# PROJECT-TSC_v66.net
KiCad netlist of a schematic drawn in EAGLE
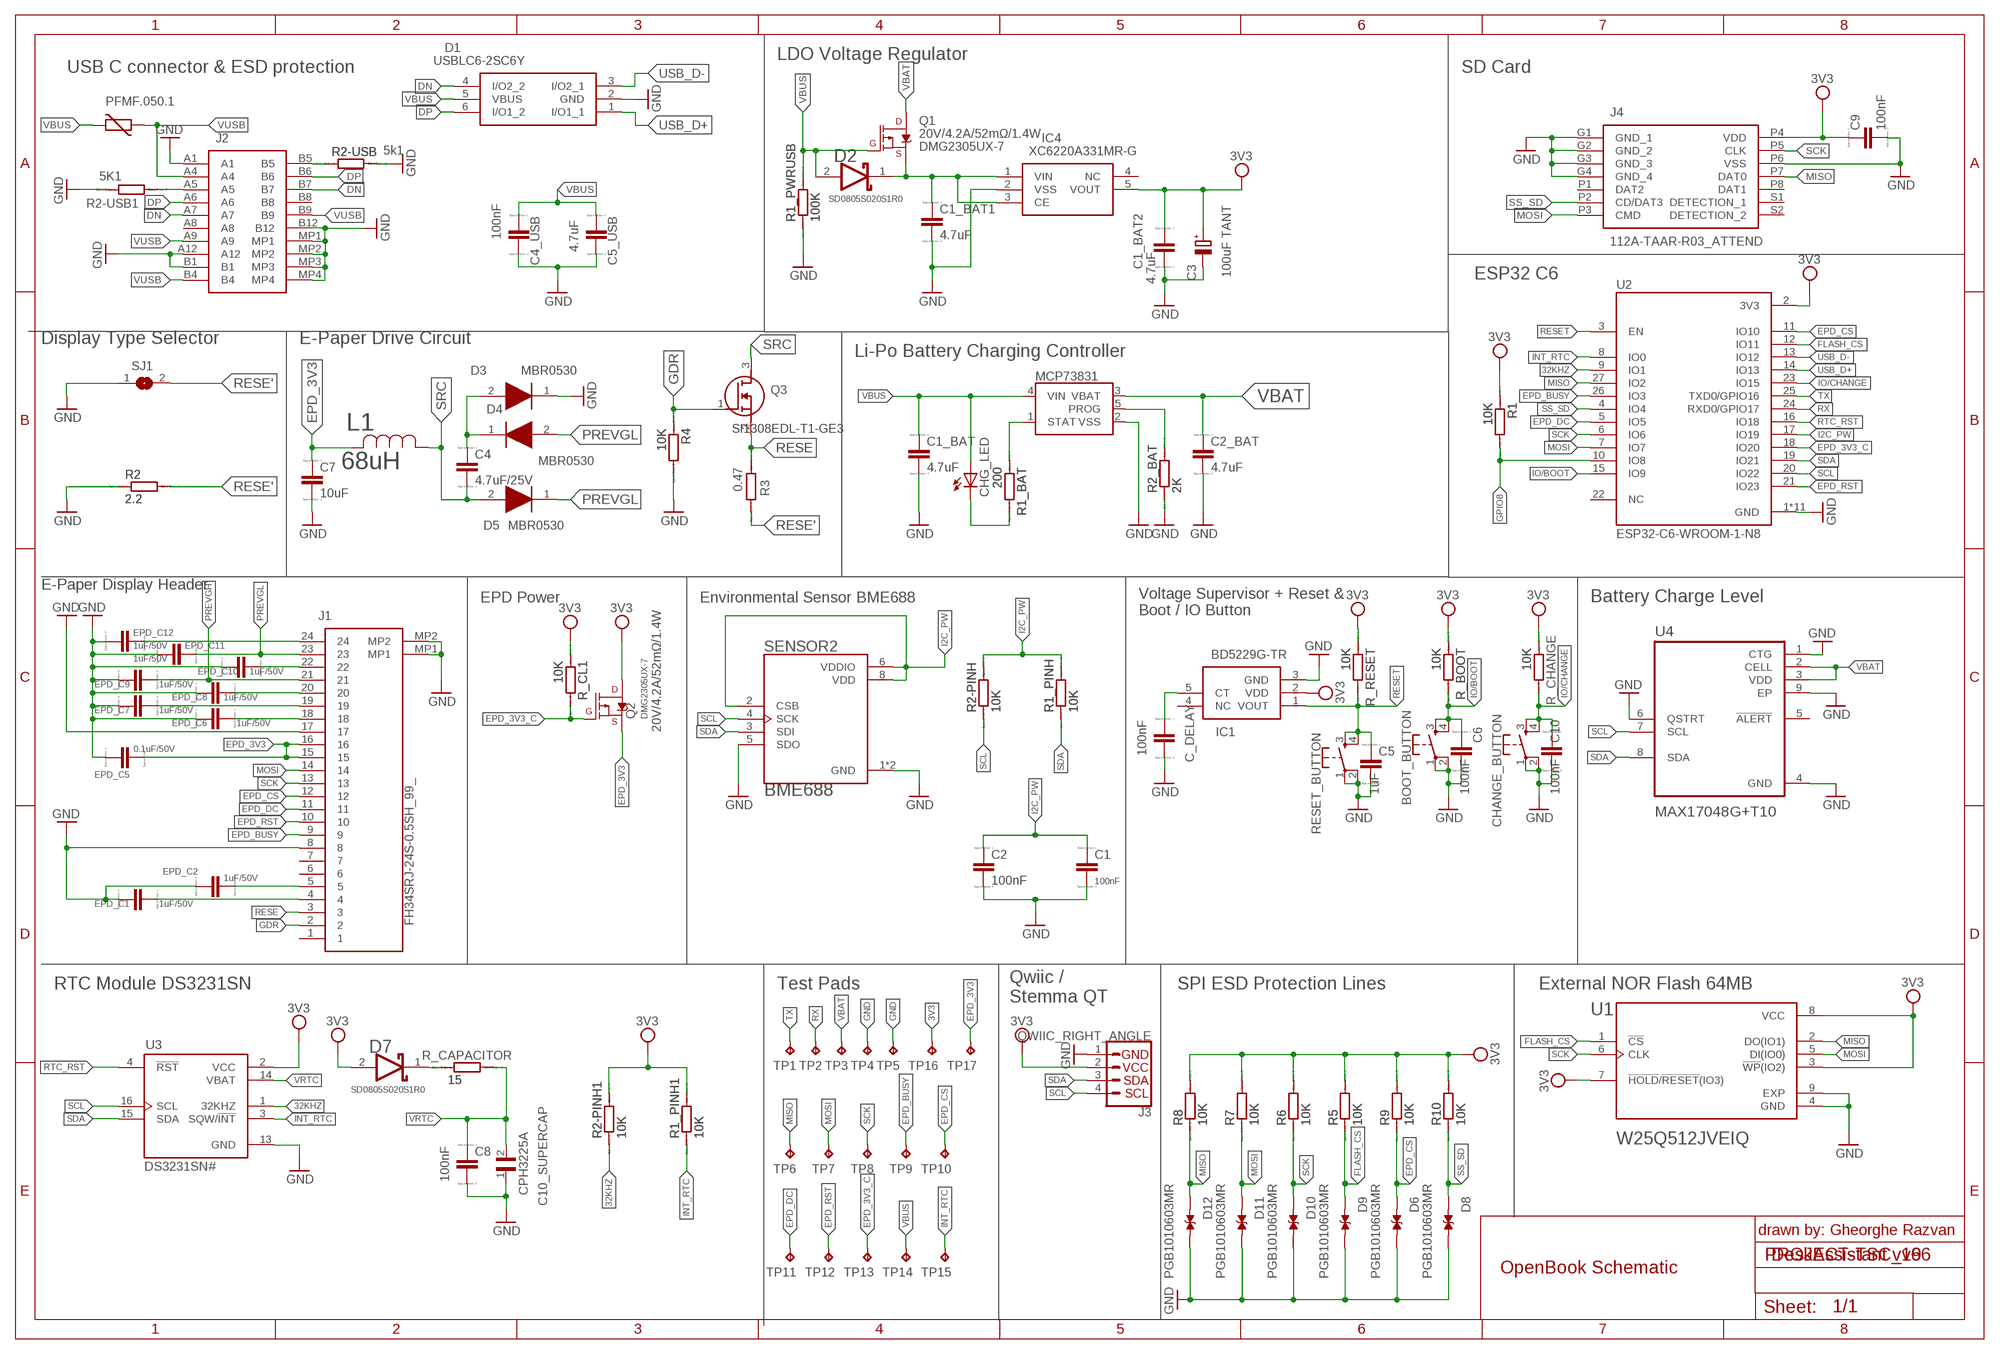
[diagram p0: schematic, sheet 1]

(export (version "E")
  (design (tool "Eeschema 10.0.6"))
  (components
    (comp (ref "BOOT_BUTTON")
      (value "BUTTON_CUSYOMV1")
      (footprint "eagle-import:MYBUTTON")
      (libsource (lib "eagle-import") (part "BUTTON_CUSYOMV1"))
    )
    (comp (ref "C1")
      (value "100nF")
      (footprint "eagle-import:EAGLE-LTSPICE_C0402")
      (libsource (lib "eagle-import") (part "EAGLE-LTSPICE_CC0402"))
    )
    (comp (ref "C1_BAT")
      (value "4.7uF")
      (footprint "eagle-import:EAGLE-LTSPICE_C0402")
      (libsource (lib "eagle-import") (part "ESP32_WROVER_EAGLE-LTSPICE_CC0402"))
    )
    (comp (ref "C1_BAT1")
      (value "4.7uF")
      (footprint "eagle-import:EAGLE-LTSPICE_C0402")
      (libsource (lib "eagle-import") (part "ESP32_WROVER_EAGLE-LTSPICE_CC0402"))
    )
    (comp (ref "C1_BAT2")
      (value "4.7uF")
      (footprint "eagle-import:EAGLE-LTSPICE_C0402")
      (libsource (lib "eagle-import") (part "ESP32_WROVER_EAGLE-LTSPICE_CC0402"))
    )
    (comp (ref "C2")
      (value "100nF")
      (footprint "eagle-import:EAGLE-LTSPICE_C0402")
      (libsource (lib "eagle-import") (part "EAGLE-LTSPICE_CC0402"))
    )
    (comp (ref "C2_BAT")
      (value "4.7uF")
      (footprint "eagle-import:EAGLE-LTSPICE_C0402")
      (libsource (lib "eagle-import") (part "ESP32_WROVER_EAGLE-LTSPICE_CC0402"))
    )
    (comp (ref "C3")
      (value "100uF TANT")
      (footprint "eagle-import:RCL_CT3528")
      (libsource (lib "eagle-import") (part "RCL_CPOL-EUCT3528"))
    )
    (comp (ref "C4")
      (value "4.7uF/25V")
      (footprint "eagle-import:EAGLE-LTSPICE_C0402")
      (libsource (lib "eagle-import") (part "ESP32_WROVER_EAGLE-LTSPICE_CC0402"))
    )
    (comp (ref "C4_USB")
      (value "100nF")
      (footprint "eagle-import:EAGLE-LTSPICE_C0402")
      (libsource (lib "eagle-import") (part "ESP32_WROVER_EAGLE-LTSPICE_CC0402"))
    )
    (comp (ref "C5")
      (value "1uF")
      (footprint "eagle-import:EAGLE-LTSPICE_C0402")
      (libsource (lib "eagle-import") (part "EAGLE-LTSPICE_CC0402"))
    )
    (comp (ref "C5_USB")
      (value "4.7uF")
      (footprint "eagle-import:EAGLE-LTSPICE_C0402")
      (libsource (lib "eagle-import") (part "ESP32_WROVER_EAGLE-LTSPICE_CC0402"))
    )
    (comp (ref "C6")
      (value "100nF")
      (footprint "eagle-import:EAGLE-LTSPICE_C0402")
      (libsource (lib "eagle-import") (part "EAGLE-LTSPICE_CC0402"))
    )
    (comp (ref "C7")
      (value "10uF")
      (footprint "eagle-import:EAGLE-LTSPICE_C0402")
      (libsource (lib "eagle-import") (part "EAGLE-LTSPICE_CC0402"))
    )
    (comp (ref "C8")
      (value "100nF")
      (footprint "eagle-import:EAGLE-LTSPICE_C0402")
      (libsource (lib "eagle-import") (part "ESP32_WROVER_EAGLE-LTSPICE_CC0402"))
    )
    (comp (ref "C9")
      (value "100nF")
      (footprint "eagle-import:EAGLE-LTSPICE_C0402")
      (libsource (lib "eagle-import") (part "ESP32_WROVER_EAGLE-LTSPICE_CC0402"))
    )
    (comp (ref "C10")
      (value "100nF")
      (footprint "eagle-import:EAGLE-LTSPICE_C0402")
      (libsource (lib "eagle-import") (part "EAGLE-LTSPICE_CC0402"))
    )
    (comp (ref "C10_SUPERCAP")
      (value "CPH3225A")
      (footprint "eagle-import:CAPCP3225X100N")
      (fields (field (name "MF") "Seiko Instruments"))
      (libsource (lib "eagle-import") (part "CPH3225A"))
    )
    (comp (ref "CHANGE_BUTTON")
      (value "BUTTON_CUSYOMV1")
      (footprint "eagle-import:MYBUTTON")
      (libsource (lib "eagle-import") (part "BUTTON_CUSYOMV1"))
    )
    (comp (ref "CHG_LED")
      (value "ADAFRUIT_LEDCHIP-LED0603")
      (footprint "eagle-import:ADAFRUIT_CHIP-LED0603")
      (libsource (lib "eagle-import") (part "ADAFRUIT_LEDCHIP-LED0603"))
    )
    (comp (ref "C_DELAY")
      (value "100nF")
      (footprint "eagle-import:EAGLE-LTSPICE_C0402")
      (libsource (lib "eagle-import") (part "EAGLE-LTSPICE_CC0402"))
    )
    (comp (ref "D1")
      (value "USBLC6-2SC6Y")
      (footprint "eagle-import:SOT95P280X145-6N")
      (fields (field (name "MF") "STMicroelectronics"))
      (libsource (lib "eagle-import") (part "USBLC6-2SC6Y"))
    )
    (comp (ref "D2")
      (value "ESP32_WROVER_AVX---SD0805S020S1R0_AVX_SD0805S020S1R0_0_0AVX_SD0805S020S1R0_0_0")
      (footprint "eagle-import:ESP32_WROVER_AVX---SD0805S020S1R0_AVX_SD0805S020S1R0_0")
      (fields
        (field (name "DIGIKEY_PART_NUMBER") "478-7800-1-ND")
        (field (name "MF") "AVX")
        (field (name "MOUSER_PART_NUMBER") "581-SD0805S020S1R0")
      )
      (libsource (lib "eagle-import") (part "ESP32_WROVER_AVX---SD0805S020S1R0_AVX_SD0805S020S1R0_0_0AVX_SD0805S020S1R0_0_0"))
    )
    (comp (ref "D3")
      (value "MBR0530")
      (footprint "eagle-import:SOD3716X135N")
      (fields (field (name "MF") "ON Semiconductor"))
      (libsource (lib "eagle-import") (part "MBR0530"))
    )
    (comp (ref "D4")
      (value "MBR0530")
      (footprint "eagle-import:SOD3716X135N")
      (fields (field (name "MF") "ON Semiconductor"))
      (libsource (lib "eagle-import") (part "MBR0530"))
    )
    (comp (ref "D5")
      (value "MBR0530")
      (footprint "eagle-import:SOD3716X135N")
      (fields (field (name "MF") "ON Semiconductor"))
      (libsource (lib "eagle-import") (part "MBR0530"))
    )
    (comp (ref "D6")
      (value "PGB1010603MR")
      (footprint "eagle-import:DIOC1608X36N")
      (fields (field (name "MF") "Littelfuse Inc."))
      (libsource (lib "eagle-import") (part "PGB1010603MR"))
    )
    (comp (ref "D7")
      (value "ESP32_WROVER_AVX---SD0805S020S1R0_AVX_SD0805S020S1R0_0_0AVX_SD0805S020S1R0_0_0")
      (footprint "eagle-import:ESP32_WROVER_AVX---SD0805S020S1R0_AVX_SD0805S020S1R0_0")
      (fields
        (field (name "DIGIKEY_PART_NUMBER") "478-7800-1-ND")
        (field (name "MF") "AVX")
        (field (name "MOUSER_PART_NUMBER") "581-SD0805S020S1R0")
      )
      (libsource (lib "eagle-import") (part "ESP32_WROVER_AVX---SD0805S020S1R0_AVX_SD0805S020S1R0_0_0AVX_SD0805S020S1R0_0_0"))
    )
    (comp (ref "D8")
      (value "PGB1010603MR")
      (footprint "eagle-import:DIOC1608X36N")
      (fields (field (name "MF") "Littelfuse Inc."))
      (libsource (lib "eagle-import") (part "PGB1010603MR"))
    )
    (comp (ref "D9")
      (value "PGB1010603MR")
      (footprint "eagle-import:DIOC1608X36N")
      (fields (field (name "MF") "Littelfuse Inc."))
      (libsource (lib "eagle-import") (part "PGB1010603MR"))
    )
    (comp (ref "D10")
      (value "PGB1010603MR")
      (footprint "eagle-import:DIOC1608X36N")
      (fields (field (name "MF") "Littelfuse Inc."))
      (libsource (lib "eagle-import") (part "PGB1010603MR"))
    )
    (comp (ref "D11")
      (value "PGB1010603MR")
      (footprint "eagle-import:DIOC1608X36N")
      (fields (field (name "MF") "Littelfuse Inc."))
      (libsource (lib "eagle-import") (part "PGB1010603MR"))
    )
    (comp (ref "D12")
      (value "PGB1010603MR")
      (footprint "eagle-import:DIOC1608X36N")
      (fields (field (name "MF") "Littelfuse Inc."))
      (libsource (lib "eagle-import") (part "PGB1010603MR"))
    )
    (comp (ref "EPD_C1")
      (value "1uF/50V")
      (footprint "eagle-import:EAGLE-LTSPICE_C0402")
      (libsource (lib "eagle-import") (part "ESP32_WROVER_EAGLE-LTSPICE_CC0402"))
    )
    (comp (ref "EPD_C2")
      (value "1uF/50V")
      (footprint "eagle-import:EAGLE-LTSPICE_C0402")
      (libsource (lib "eagle-import") (part "ESP32_WROVER_EAGLE-LTSPICE_CC0402"))
    )
    (comp (ref "EPD_C5")
      (value "0.1uF/50V")
      (footprint "eagle-import:EAGLE-LTSPICE_C0402")
      (libsource (lib "eagle-import") (part "ESP32_WROVER_EAGLE-LTSPICE_CC0402"))
    )
    (comp (ref "EPD_C6")
      (value "1uF/50V")
      (footprint "eagle-import:EAGLE-LTSPICE_C0402")
      (libsource (lib "eagle-import") (part "ESP32_WROVER_EAGLE-LTSPICE_CC0402"))
    )
    (comp (ref "EPD_C7")
      (value "1uF/50V")
      (footprint "eagle-import:EAGLE-LTSPICE_C0402")
      (libsource (lib "eagle-import") (part "ESP32_WROVER_EAGLE-LTSPICE_CC0402"))
    )
    (comp (ref "EPD_C8")
      (value "1uF/50V")
      (footprint "eagle-import:EAGLE-LTSPICE_C0402")
      (libsource (lib "eagle-import") (part "ESP32_WROVER_EAGLE-LTSPICE_CC0402"))
    )
    (comp (ref "EPD_C9")
      (value "1uF/50V")
      (footprint "eagle-import:EAGLE-LTSPICE_C0402")
      (libsource (lib "eagle-import") (part "ESP32_WROVER_EAGLE-LTSPICE_CC0402"))
    )
    (comp (ref "EPD_C10")
      (value "1uF/50V")
      (footprint "eagle-import:EAGLE-LTSPICE_C0402")
      (libsource (lib "eagle-import") (part "ESP32_WROVER_EAGLE-LTSPICE_CC0402"))
    )
    (comp (ref "EPD_C11")
      (value "1uF/50V")
      (footprint "eagle-import:EAGLE-LTSPICE_C0402")
      (libsource (lib "eagle-import") (part "ESP32_WROVER_EAGLE-LTSPICE_CC0402"))
    )
    (comp (ref "EPD_C12")
      (value "1uF/50V")
      (footprint "eagle-import:EAGLE-LTSPICE_C0402")
      (libsource (lib "eagle-import") (part "ESP32_WROVER_EAGLE-LTSPICE_CC0402"))
    )
    (comp (ref "IC1")
      (value "BD5229G-TR")
      (footprint "eagle-import:SOT95P280X120-5N")
      (fields (field (name "MOUSER_PART_NUMBER") "755-BD5229G-TR"))
      (libsource (lib "eagle-import") (part "BD5229G-TR"))
    )
    (comp (ref "IC4")
      (value "XC6220A331MR-G")
      (footprint "eagle-import:SOT95P280X120-5N")
      (fields (field (name "MOUSER_PART_NUMBER") "865-XC6220A331MR-G"))
      (libsource (lib "eagle-import") (part "XC6220A331MR-G"))
    )
    (comp (ref "J1")
      (value "FH34SRJ-24S-0.5SH_99_")
      (footprint "eagle-import:FH34SRJ24S05SH99")
      (fields
        (field (name "MANUFACTURER_PART_NUMBER") "FH34SRJ-24S-0.5SH(99)")
        (field (name "MOUSER_PART_NUMBER") "798-FH34SRJ24S05SH99")
      )
      (libsource (lib "eagle-import") (part "FH34SRJ-24S-0.5SH_99_"))
    )
    (comp (ref "J2")
      (value "SAMACSYS_PARTS_USB4110-GF-A")
      (footprint "eagle-import:SAMACSYS_PARTS_USB4110GFA")
      (fields
        (field (name "MANUFACTURER_PART_NUMBER") "USB4110-GF-A")
        (field (name "MOUSER_PART_NUMBER") "640-USB4110-GF-A")
      )
      (libsource (lib "eagle-import") (part "SAMACSYS_PARTS_USB4110-GF-A"))
    )
    (comp (ref "J3")
      (value "QWIIC_RIGHT_ANGLE")
      (footprint "eagle-import:JST04_1MM_RA")
      (libsource (lib "eagle-import") (part "QWIIC_CONNECTORJS-1MM"))
    )
    (comp (ref "J4")
      (value "112A-TAAR-R03_ATTEND")
      (footprint "eagle-import:112ATAARR03ATTEND")
      (fields (field (name "MANUFACTURER_PART_NUMBER") "112A-TAAR-R03 ATTEND"))
      (libsource (lib "eagle-import") (part "112A-TAAR-R03_ATTEND"))
    )
    (comp (ref "L1")
      (value "68uH")
      (footprint "eagle-import:IND_4828-WE-TPC_WRE")
      (fields
        (field (name "MANUFACTURER_PART_NUMBER") "744043680")
        (field (name "COPYRIGHT") "Copyright (C) 2024 Ultra Librarian. All rights reserved.")
      )
      (libsource (lib "eagle-import") (part "744043680IND_4828-WE-TPC_WRE"))
    )
    (comp (ref "MCP73831")
      (value "ESP32_WROVER_SPARKFUN-IC-POWER_MCP73831")
      (footprint "eagle-import:ESP32_WROVER_SPARKFUN-IC-POWER_SOT23-5")
      (libsource (lib "eagle-import") (part "ESP32_WROVER_SPARKFUN-IC-POWER_MCP73831"))
    )
    (comp (ref "PFMF.050.1")
      (value "ESP32C6_VARISTORCN1812")
      (footprint "eagle-import:ESP32C6_VARISTOR_CT_CN1812")
      (libsource (lib "eagle-import") (part "ESP32C6_VARISTORCN1812"))
    )
    (comp (ref "Q1")
      (value "20V/4.2A/52mΩ/1.4W")
      (footprint "eagle-import:ESP32_WROVER_SPARKFUN-DISCRETESEMI_SOT23-3")
      (libsource (lib "eagle-import") (part "ESP32_WROVER_SPARKFUN-DISCRETESEMI_MOSFET_PCH-DMG2305UX-7"))
    )
    (comp (ref "Q2")
      (value "20V/4.2A/52mΩ/1.4W")
      (footprint "eagle-import:ESP32_WROVER_SPARKFUN-DISCRETESEMI_SOT23-3")
      (libsource (lib "eagle-import") (part "ESP32_WROVER_SPARKFUN-DISCRETESEMI_MOSFET_PCH-DMG2305UX-7"))
    )
    (comp (ref "Q3")
      (value "SI1308EDL-T1-GE3")
      (footprint "eagle-import:SOT65P210X110-3N")
      (fields (field (name "MF") "Vishay Siliconix"))
      (libsource (lib "eagle-import") (part "SI1308EDL-T1-GE3"))
    )
    (comp (ref "R1")
      (value "10K")
      (footprint "eagle-import:ESP32_WROVER_EAGLE-LTSPICE_R0402")
      (libsource (lib "eagle-import") (part "ESP32_WROVER_EAGLE-LTSPICE_RR0402"))
    )
    (comp (ref "R1_BAT")
      (value "200")
      (footprint "eagle-import:ESP32_WROVER_EAGLE-LTSPICE_R0402")
      (libsource (lib "eagle-import") (part "ESP32_WROVER_EAGLE-LTSPICE_RR0402"))
    )
    (comp (ref "R1_PINH")
      (value "10K")
      (footprint "eagle-import:ESP32_WROVER_EAGLE-LTSPICE_R0402")
      (libsource (lib "eagle-import") (part "ESP32_WROVER_EAGLE-LTSPICE_RR0402"))
    )
    (comp (ref "R1_PINH1")
      (value "10K")
      (footprint "eagle-import:ESP32_WROVER_EAGLE-LTSPICE_R0402")
      (libsource (lib "eagle-import") (part "ESP32_WROVER_EAGLE-LTSPICE_RR0402"))
    )
    (comp (ref "R1_PWRUSB")
      (value "100K")
      (footprint "eagle-import:ESP32_WROVER_EAGLE-LTSPICE_R0402")
      (libsource (lib "eagle-import") (part "ESP32_WROVER_EAGLE-LTSPICE_RR0402"))
    )
    (comp (ref "R2")
      (value "2.2")
      (footprint "eagle-import:ESP32_WROVER_EAGLE-LTSPICE_R0402")
      (libsource (lib "eagle-import") (part "ESP32_WROVER_EAGLE-LTSPICE_RR0402"))
    )
    (comp (ref "R2-PINH")
      (value "10K")
      (footprint "eagle-import:ESP32_WROVER_EAGLE-LTSPICE_R0402")
      (libsource (lib "eagle-import") (part "ESP32_WROVER_EAGLE-LTSPICE_RR0402"))
    )
    (comp (ref "R2-PINH1")
      (value "10K")
      (footprint "eagle-import:ESP32_WROVER_EAGLE-LTSPICE_R0402")
      (libsource (lib "eagle-import") (part "ESP32_WROVER_EAGLE-LTSPICE_RR0402"))
    )
    (comp (ref "R2-USB")
      (value "5k1")
      (footprint "eagle-import:ESP32_WROVER_EAGLE-LTSPICE_R0402")
      (libsource (lib "eagle-import") (part "ESP32_WROVER_EAGLE-LTSPICE_RR0402"))
    )
    (comp (ref "R2-USB1")
      (value "5K1")
      (footprint "eagle-import:ESP32_WROVER_EAGLE-LTSPICE_R0402")
      (libsource (lib "eagle-import") (part "ESP32_WROVER_EAGLE-LTSPICE_RR0402"))
    )
    (comp (ref "R2_BAT")
      (value "2K")
      (footprint "eagle-import:ESP32_WROVER_EAGLE-LTSPICE_R0402")
      (libsource (lib "eagle-import") (part "ESP32_WROVER_EAGLE-LTSPICE_RR0402"))
    )
    (comp (ref "R3")
      (value "0.47")
      (footprint "eagle-import:ESP32_WROVER_EAGLE-LTSPICE_R0402")
      (libsource (lib "eagle-import") (part "ESP32_WROVER_EAGLE-LTSPICE_RR0402"))
    )
    (comp (ref "R4")
      (value "10K")
      (footprint "eagle-import:ESP32_WROVER_EAGLE-LTSPICE_R0402")
      (libsource (lib "eagle-import") (part "ESP32_WROVER_EAGLE-LTSPICE_RR0402"))
    )
    (comp (ref "R5")
      (value "10K")
      (footprint "eagle-import:ESP32_WROVER_EAGLE-LTSPICE_R0402")
      (libsource (lib "eagle-import") (part "ESP32_WROVER_EAGLE-LTSPICE_RR0402"))
    )
    (comp (ref "R6")
      (value "10K")
      (footprint "eagle-import:ESP32_WROVER_EAGLE-LTSPICE_R0402")
      (libsource (lib "eagle-import") (part "ESP32_WROVER_EAGLE-LTSPICE_RR0402"))
    )
    (comp (ref "R7")
      (value "10K")
      (footprint "eagle-import:ESP32_WROVER_EAGLE-LTSPICE_R0402")
      (libsource (lib "eagle-import") (part "ESP32_WROVER_EAGLE-LTSPICE_RR0402"))
    )
    (comp (ref "R8")
      (value "10K")
      (footprint "eagle-import:ESP32_WROVER_EAGLE-LTSPICE_R0402")
      (libsource (lib "eagle-import") (part "ESP32_WROVER_EAGLE-LTSPICE_RR0402"))
    )
    (comp (ref "R9")
      (value "10K")
      (footprint "eagle-import:ESP32_WROVER_EAGLE-LTSPICE_R0402")
      (libsource (lib "eagle-import") (part "ESP32_WROVER_EAGLE-LTSPICE_RR0402"))
    )
    (comp (ref "R10")
      (value "10K")
      (footprint "eagle-import:ESP32_WROVER_EAGLE-LTSPICE_R0402")
      (libsource (lib "eagle-import") (part "ESP32_WROVER_EAGLE-LTSPICE_RR0402"))
    )
    (comp (ref "RESET_BUTTON")
      (value "BUTTON_CUSYOMV1")
      (footprint "eagle-import:MYBUTTON")
      (libsource (lib "eagle-import") (part "BUTTON_CUSYOMV1"))
    )
    (comp (ref "R_BOOT")
      (value "10K")
      (footprint "eagle-import:ESP32_WROVER_EAGLE-LTSPICE_R0402")
      (libsource (lib "eagle-import") (part "ESP32_WROVER_EAGLE-LTSPICE_RR0402"))
    )
    (comp (ref "R_CAPACITOR")
      (value "15")
      (footprint "eagle-import:ESP32_WROVER_EAGLE-LTSPICE_R0402")
      (libsource (lib "eagle-import") (part "ESP32_WROVER_EAGLE-LTSPICE_RR0402"))
    )
    (comp (ref "R_CHANGE")
      (value "10K")
      (footprint "eagle-import:ESP32_WROVER_EAGLE-LTSPICE_R0402")
      (libsource (lib "eagle-import") (part "ESP32_WROVER_EAGLE-LTSPICE_RR0402"))
    )
    (comp (ref "R_CL1")
      (value "10K")
      (footprint "eagle-import:ESP32_WROVER_EAGLE-LTSPICE_R0402")
      (libsource (lib "eagle-import") (part "ESP32_WROVER_EAGLE-LTSPICE_RR0402"))
    )
    (comp (ref "R_RESET")
      (value "10K")
      (footprint "eagle-import:ESP32_WROVER_EAGLE-LTSPICE_R0402")
      (libsource (lib "eagle-import") (part "ESP32_WROVER_EAGLE-LTSPICE_RR0402"))
    )
    (comp (ref "SENSOR2")
      (value "ESP32_WROVER_BME680_BME680")
      (footprint "eagle-import:ESP32_WROVER_BME680_PSON80P300X300X100-8N")
      (fields (field (name "MF") "Bosch Sensortec") (field (name "MP") "BME680"))
      (libsource (lib "eagle-import") (part "ESP32_WROVER_BME680_BME680"))
    )
    (comp (ref "SJ1") (value "SJ") (footprint "eagle-import:SJ") (libsource (lib "eagle-import") (part "SJ")))
    (comp (ref "TP1")
      (value "TPTP20R")
      (footprint "eagle-import:TP20R")
      (libsource (lib "eagle-import") (part "TPTP20R"))
    )
    (comp (ref "TP2")
      (value "TPTP20R")
      (footprint "eagle-import:TP20R")
      (libsource (lib "eagle-import") (part "TPTP20R"))
    )
    (comp (ref "TP3")
      (value "TPTP20R")
      (footprint "eagle-import:TP20R")
      (libsource (lib "eagle-import") (part "TPTP20R"))
    )
    (comp (ref "TP4")
      (value "TPTP20R")
      (footprint "eagle-import:TP20R")
      (libsource (lib "eagle-import") (part "TPTP20R"))
    )
    (comp (ref "TP5")
      (value "TPTP20R")
      (footprint "eagle-import:TP20R")
      (libsource (lib "eagle-import") (part "TPTP20R"))
    )
    (comp (ref "TP6")
      (value "TPTP20R")
      (footprint "eagle-import:TP20R")
      (libsource (lib "eagle-import") (part "TPTP20R"))
    )
    (comp (ref "TP7")
      (value "TPTP20R")
      (footprint "eagle-import:TP20R")
      (libsource (lib "eagle-import") (part "TPTP20R"))
    )
    (comp (ref "TP8")
      (value "TPTP20R")
      (footprint "eagle-import:TP20R")
      (libsource (lib "eagle-import") (part "TPTP20R"))
    )
    (comp (ref "TP9")
      (value "TPTP20R")
      (footprint "eagle-import:TP20R")
      (libsource (lib "eagle-import") (part "TPTP20R"))
    )
    (comp (ref "TP10")
      (value "TPTP20R")
      (footprint "eagle-import:TP20R")
      (libsource (lib "eagle-import") (part "TPTP20R"))
    )
    (comp (ref "TP11")
      (value "TPTP20R")
      (footprint "eagle-import:TP20R")
      (libsource (lib "eagle-import") (part "TPTP20R"))
    )
    (comp (ref "TP12")
      (value "TPTP20R")
      (footprint "eagle-import:TP20R")
      (libsource (lib "eagle-import") (part "TPTP20R"))
    )
    (comp (ref "TP13")
      (value "TPTP20R")
      (footprint "eagle-import:TP20R")
      (libsource (lib "eagle-import") (part "TPTP20R"))
    )
    (comp (ref "TP14")
      (value "TPTP20R")
      (footprint "eagle-import:TP20R")
      (libsource (lib "eagle-import") (part "TPTP20R"))
    )
    (comp (ref "TP15")
      (value "TPTP20R")
      (footprint "eagle-import:TP20R")
      (libsource (lib "eagle-import") (part "TPTP20R"))
    )
    (comp (ref "TP16")
      (value "TPTP20R")
      (footprint "eagle-import:TP20R")
      (libsource (lib "eagle-import") (part "TPTP20R"))
    )
    (comp (ref "TP17")
      (value "TPTP20R")
      (footprint "eagle-import:TP20R")
      (libsource (lib "eagle-import") (part "TPTP20R"))
    )
    (comp (ref "U1")
      (value "W25Q512JVEIQ")
      (footprint "eagle-import:SON127P600X800X80-9N")
      (fields (field (name "MF") "Winbond Electronics"))
      (libsource (lib "eagle-import") (part "W25Q512JVEIQ"))
    )
    (comp (ref "U2")
      (value "ESP32-C6-WROOM-1-N8")
      (footprint "eagle-import:XCVR_ESP32-C6-WROOM-1-N8")
      (fields (field (name "MF") "Espressif Systems"))
      (libsource (lib "eagle-import") (part "ESP32-C6-WROOM-1-N8"))
    )
    (comp (ref "U3")
      (value "DS3231SN#")
      (footprint "eagle-import:SOIC127P1032X265-16N")
      (fields (field (name "MF") "Analog Devices"))
      (libsource (lib "eagle-import") (part "DS3231SN#"))
    )
    (comp (ref "U4")
      (value "MAX17048G+T10")
      (footprint "eagle-import:SON50P200X200X80-9N")
      (fields (field (name "MF") "Analog Devices"))
      (libsource (lib "eagle-import") (part "MAX17048G+T10"))
    )
  )
  (nets
    (net (code "1") (name "3V3") (class "Default")
      (node (ref "C1_BAT2") (pin "1") (pinfunction "1_1") (pintype "passive"))
      (node (ref "C3") (pin "+") (pinfunction "+_+") (pintype "passive"))
      (node (ref "C9") (pin "1") (pinfunction "1_1") (pintype "passive"))
      (node (ref "D7") (pin "2") (pinfunction "ANODE_2") (pintype "bidirectional"))
      (node (ref "IC1") (pin "2") (pinfunction "VDD_2") (pintype "bidirectional"))
      (node (ref "IC4") (pin "5") (pinfunction "VOUT_5") (pintype "bidirectional"))
      (node (ref "J3") (pin "2") (pinfunction "2_2") (pintype "power_in"))
      (node (ref "J4") (pin "P4") (pinfunction "VDD_P4") (pintype "bidirectional"))
      (node (ref "Q2") (pin "3") (pinfunction "D_3") (pintype "bidirectional"))
      (node (ref "R1") (pin "1") (pinfunction "1_1") (pintype "passive"))
      (node (ref "R10") (pin "2") (pinfunction "2_2") (pintype "passive"))
      (node (ref "R1_PINH1") (pin "2") (pinfunction "2_2") (pintype "passive"))
      (node (ref "R2-PINH1") (pin "2") (pinfunction "2_2") (pintype "passive"))
      (node (ref "R5") (pin "2") (pinfunction "2_2") (pintype "passive"))
      (node (ref "R6") (pin "2") (pinfunction "2_2") (pintype "passive"))
      (node (ref "R7") (pin "2") (pinfunction "2_2") (pintype "passive"))
      (node (ref "R8") (pin "2") (pinfunction "2_2") (pintype "passive"))
      (node (ref "R9") (pin "2") (pinfunction "2_2") (pintype "passive"))
      (node (ref "R_BOOT") (pin "1") (pinfunction "1_1") (pintype "passive"))
      (node (ref "R_CHANGE") (pin "1") (pinfunction "1_1") (pintype "passive"))
      (node (ref "R_CL1") (pin "1") (pinfunction "1_1") (pintype "passive"))
      (node (ref "R_RESET") (pin "1") (pinfunction "1_1") (pintype "passive"))
      (node (ref "TP16") (pin "TP") (pinfunction "TP_TP") (pintype "input"))
      (node (ref "U1") (pin "3") (pinfunction "~{WP}(IO2)_3") (pintype "bidirectional"))
      (node (ref "U1") (pin "7") (pinfunction "~{HOLD}/~{RESET}(IO3)_7") (pintype "bidirectional"))
      (node (ref "U1") (pin "8") (pinfunction "VCC_8") (pintype "power_in"))
      (node (ref "U2") (pin "2") (pinfunction "3V3_2") (pintype "power_in"))
      (node (ref "U3") (pin "2") (pinfunction "VCC_2") (pintype "power_in"))
    )
    (net (code "2") (name "32KHZ") (class "Default")
      (node (ref "R2-PINH1") (pin "1") (pinfunction "1_1") (pintype "passive"))
      (node (ref "U2") (pin "9") (pinfunction "IO1_9") (pintype "bidirectional"))
      (node (ref "U3") (pin "1") (pinfunction "32KHZ_1") (pintype "output"))
    )
    (net (code "3") (name "DN") (class "Default")
      (node (ref "D1") (pin "4") (pinfunction "I/O2_2_4") (pintype "bidirectional"))
      (node (ref "J2") (pin "A7") (pinfunction "A7_A7") (pintype "bidirectional"))
      (node (ref "J2") (pin "B7") (pinfunction "B7_B7") (pintype "bidirectional"))
    )
    (net (code "4") (name "DP") (class "Default")
      (node (ref "D1") (pin "6") (pinfunction "I/O1_2_6") (pintype "bidirectional"))
      (node (ref "J2") (pin "A6") (pinfunction "A6_A6") (pintype "bidirectional"))
      (node (ref "J2") (pin "B6") (pinfunction "B6_B6") (pintype "bidirectional"))
    )
    (net (code "5") (name "EPD_3V3") (class "Default")
      (node (ref "C7") (pin "1") (pinfunction "1_1") (pintype "passive"))
      (node (ref "EPD_C5") (pin "1") (pinfunction "1_1") (pintype "passive"))
      (node (ref "J1") (pin "15") (pinfunction "15_15") (pintype "bidirectional"))
      (node (ref "J1") (pin "16") (pinfunction "16_16") (pintype "bidirectional"))
      (node (ref "L1") (pin "2") (pinfunction "2_2") (pintype "passive"))
      (node (ref "Q2") (pin "2") (pinfunction "S_2") (pintype "bidirectional"))
      (node (ref "TP17") (pin "TP") (pinfunction "TP_TP") (pintype "input"))
    )
    (net (code "6") (name "EPD_3V3_C") (class "Default")
      (node (ref "Q2") (pin "1") (pinfunction "G_1") (pintype "bidirectional"))
      (node (ref "R_CL1") (pin "2") (pinfunction "2_2") (pintype "passive"))
      (node (ref "TP13") (pin "TP") (pinfunction "TP_TP") (pintype "input"))
      (node (ref "U2") (pin "18") (pinfunction "IO20_18") (pintype "bidirectional"))
    )
    (net (code "7") (name "EPD_BUSY") (class "Default")
      (node (ref "J1") (pin "9") (pinfunction "9_9") (pintype "bidirectional"))
      (node (ref "TP9") (pin "TP") (pinfunction "TP_TP") (pintype "input"))
      (node (ref "U2") (pin "26") (pinfunction "IO3_26") (pintype "bidirectional"))
    )
    (net (code "8") (name "EPD_CS") (class "Default")
      (node (ref "D6") (pin "1") (pinfunction "1_1") (pintype "passive"))
      (node (ref "J1") (pin "12") (pinfunction "12_12") (pintype "bidirectional"))
      (node (ref "R9") (pin "1") (pinfunction "1_1") (pintype "passive"))
      (node (ref "TP10") (pin "TP") (pinfunction "TP_TP") (pintype "input"))
      (node (ref "U2") (pin "11") (pinfunction "IO10_11") (pintype "bidirectional"))
    )
    (net (code "9") (name "EPD_DC") (class "Default")
      (node (ref "J1") (pin "11") (pinfunction "11_11") (pintype "bidirectional"))
      (node (ref "TP11") (pin "TP") (pinfunction "TP_TP") (pintype "input"))
      (node (ref "U2") (pin "5") (pinfunction "IO5_5") (pintype "bidirectional"))
    )
    (net (code "10") (name "EPD_RST") (class "Default")
      (node (ref "J1") (pin "10") (pinfunction "10_10") (pintype "bidirectional"))
      (node (ref "TP12") (pin "TP") (pinfunction "TP_TP") (pintype "input"))
      (node (ref "U2") (pin "21") (pinfunction "IO23_21") (pintype "bidirectional"))
    )
    (net (code "11") (name "FLASH_CS") (class "Default")
      (node (ref "D9") (pin "1") (pinfunction "1_1") (pintype "passive"))
      (node (ref "R5") (pin "1") (pinfunction "1_1") (pintype "passive"))
      (node (ref "U1") (pin "1") (pinfunction "~{CS}_1") (pintype "input"))
      (node (ref "U2") (pin "12") (pinfunction "IO11_12") (pintype "bidirectional"))
    )
    (net (code "12") (name "GDR") (class "Default")
      (node (ref "J1") (pin "2") (pinfunction "2_2") (pintype "bidirectional"))
      (node (ref "Q3") (pin "1") (pinfunction "G_1") (pintype "bidirectional"))
      (node (ref "R4") (pin "1") (pinfunction "1_1") (pintype "passive"))
    )
    (net (code "13") (name "GND") (class "Default")
      (node (ref "BOOT_BUTTON") (pin "1") (pinfunction "1_1") (pintype "passive"))
      (node (ref "BOOT_BUTTON") (pin "2") (pinfunction "2_2") (pintype "passive"))
      (node (ref "C1") (pin "2") (pinfunction "2_2") (pintype "passive"))
      (node (ref "C10") (pin "2") (pinfunction "2_2") (pintype "passive"))
      (node (ref "C10_SUPERCAP") (pin "1") (pinfunction "1_1") (pintype "passive"))
      (node (ref "C1_BAT") (pin "2") (pinfunction "2_2") (pintype "passive"))
      (node (ref "C1_BAT1") (pin "2") (pinfunction "2_2") (pintype "passive"))
      (node (ref "C1_BAT2") (pin "2") (pinfunction "2_2") (pintype "passive"))
      (node (ref "C2") (pin "2") (pinfunction "2_2") (pintype "passive"))
      (node (ref "C2_BAT") (pin "2") (pinfunction "2_2") (pintype "passive"))
      (node (ref "C3") (pin "-") (pinfunction "-_-") (pintype "passive"))
      (node (ref "C4_USB") (pin "2") (pinfunction "2_2") (pintype "passive"))
      (node (ref "C5") (pin "2") (pinfunction "2_2") (pintype "passive"))
      (node (ref "C5_USB") (pin "2") (pinfunction "2_2") (pintype "passive"))
      (node (ref "C6") (pin "2") (pinfunction "2_2") (pintype "passive"))
      (node (ref "C7") (pin "2") (pinfunction "2_2") (pintype "passive"))
      (node (ref "C8") (pin "2") (pinfunction "2_2") (pintype "passive"))
      (node (ref "C9") (pin "2") (pinfunction "2_2") (pintype "passive"))
      (node (ref "CHANGE_BUTTON") (pin "1") (pinfunction "1_1") (pintype "passive"))
      (node (ref "CHANGE_BUTTON") (pin "2") (pinfunction "2_2") (pintype "passive"))
      (node (ref "C_DELAY") (pin "2") (pinfunction "2_2") (pintype "passive"))
      (node (ref "D1") (pin "2") (pinfunction "GND_2") (pintype "bidirectional"))
      (node (ref "D10") (pin "2") (pinfunction "2_2") (pintype "passive"))
      (node (ref "D11") (pin "2") (pinfunction "2_2") (pintype "passive"))
      (node (ref "D12") (pin "2") (pinfunction "2_2") (pintype "passive"))
      (node (ref "D3") (pin "1") (pinfunction "K_1") (pintype "bidirectional"))
      (node (ref "D6") (pin "2") (pinfunction "2_2") (pintype "passive"))
      (node (ref "D8") (pin "2") (pinfunction "2_2") (pintype "passive"))
      (node (ref "D9") (pin "2") (pinfunction "2_2") (pintype "passive"))
      (node (ref "EPD_C1") (pin "2") (pinfunction "2_2") (pintype "passive"))
      (node (ref "EPD_C10") (pin "2") (pinfunction "2_2") (pintype "passive"))
      (node (ref "EPD_C11") (pin "2") (pinfunction "2_2") (pintype "passive"))
      (node (ref "EPD_C12") (pin "2") (pinfunction "2_2") (pintype "passive"))
      (node (ref "EPD_C2") (pin "2") (pinfunction "2_2") (pintype "passive"))
      (node (ref "EPD_C5") (pin "2") (pinfunction "2_2") (pintype "passive"))
      (node (ref "EPD_C6") (pin "2") (pinfunction "2_2") (pintype "passive"))
      (node (ref "EPD_C7") (pin "2") (pinfunction "2_2") (pintype "passive"))
      (node (ref "EPD_C8") (pin "2") (pinfunction "2_2") (pintype "passive"))
      (node (ref "EPD_C9") (pin "2") (pinfunction "2_2") (pintype "passive"))
      (node (ref "IC1") (pin "3") (pinfunction "GND_3") (pintype "bidirectional"))
      (node (ref "IC4") (pin "2") (pinfunction "VSS_2") (pintype "bidirectional"))
      (node (ref "J1") (pin "17") (pinfunction "17_17") (pintype "bidirectional"))
      (node (ref "J1") (pin "8") (pinfunction "8_8") (pintype "bidirectional"))
      (node (ref "J1") (pin "MP1") (pinfunction "MP1_MP1") (pintype "bidirectional"))
      (node (ref "J1") (pin "MP2") (pinfunction "MP2_MP2") (pintype "bidirectional"))
      (node (ref "J2") (pin "A1") (pinfunction "A1_A1") (pintype "bidirectional"))
      (node (ref "J2") (pin "A12") (pinfunction "A12_A12") (pintype "bidirectional"))
      (node (ref "J2") (pin "B1") (pinfunction "B1_B1") (pintype "bidirectional"))
      (node (ref "J2") (pin "B12") (pinfunction "B12_B12") (pintype "bidirectional"))
      (node (ref "J2") (pin "MP1") (pinfunction "MP1_MP1") (pintype "bidirectional"))
      (node (ref "J2") (pin "MP2") (pinfunction "MP2_MP2") (pintype "bidirectional"))
      (node (ref "J2") (pin "MP3") (pinfunction "MP3_MP3") (pintype "bidirectional"))
      (node (ref "J2") (pin "MP4") (pinfunction "MP4_MP4") (pintype "bidirectional"))
      (node (ref "J3") (pin "1") (pinfunction "1_1") (pintype "power_in"))
      (node (ref "J4") (pin "G1") (pinfunction "GND_1_G1") (pintype "bidirectional"))
      (node (ref "J4") (pin "G2") (pinfunction "GND_2_G2") (pintype "bidirectional"))
      (node (ref "J4") (pin "G3") (pinfunction "GND_3_G3") (pintype "bidirectional"))
      (node (ref "J4") (pin "G4") (pinfunction "GND_4_G4") (pintype "bidirectional"))
      (node (ref "J4") (pin "P6") (pinfunction "VSS_P6") (pintype "bidirectional"))
      (node (ref "MCP73831") (pin "2") (pinfunction "VSS_2") (pintype "power_in"))
      (node (ref "R1_PWRUSB") (pin "1") (pinfunction "1_1") (pintype "passive"))
      (node (ref "R2") (pin "1") (pinfunction "1_1") (pintype "passive"))
      (node (ref "R2-USB") (pin "2") (pinfunction "2_2") (pintype "passive"))
      (node (ref "R2-USB1") (pin "1") (pinfunction "1_1") (pintype "passive"))
      (node (ref "R2_BAT") (pin "1") (pinfunction "1_1") (pintype "passive"))
      (node (ref "R4") (pin "2") (pinfunction "2_2") (pintype "passive"))
      (node (ref "RESET_BUTTON") (pin "1") (pinfunction "1_1") (pintype "passive"))
      (node (ref "RESET_BUTTON") (pin "2") (pinfunction "2_2") (pintype "passive"))
      (node (ref "SENSOR2") (pin "1") (pinfunction "GND_1") (pintype "power_in"))
      (node (ref "SENSOR2") (pin "5") (pinfunction "SDO_5") (pintype "bidirectional"))
      (node (ref "SENSOR2") (pin "7") (pinfunction "GND_7") (pintype "power_in"))
      (node (ref "SJ1") (pin "1") (pinfunction "1_1") (pintype "passive"))
      (node (ref "TP4") (pin "TP") (pinfunction "TP_TP") (pintype "input"))
      (node (ref "TP5") (pin "TP") (pinfunction "TP_TP") (pintype "input"))
      (node (ref "U1") (pin "4") (pinfunction "GND_4") (pintype "power_in"))
      (node (ref "U1") (pin "9") (pinfunction "EXP_9") (pintype "passive"))
      (node (ref "U2") (pin "1") (pinfunction "GND_1") (pintype "power_in"))
      (node (ref "U2") (pin "28") (pinfunction "GND_28") (pintype "power_in"))
      (node (ref "U2") (pin "29_1") (pinfunction "GND_29_1") (pintype "power_in"))
      (node (ref "U2") (pin "29_2") (pinfunction "GND_29_2") (pintype "power_in"))
      (node (ref "U2") (pin "29_3") (pinfunction "GND_29_3") (pintype "power_in"))
      (node (ref "U2") (pin "29_4") (pinfunction "GND_29_4") (pintype "power_in"))
      (node (ref "U2") (pin "29_5") (pinfunction "GND_29_5") (pintype "power_in"))
      (node (ref "U2") (pin "29_6") (pinfunction "GND_29_6") (pintype "power_in"))
      (node (ref "U2") (pin "29_7") (pinfunction "GND_29_7") (pintype "power_in"))
      (node (ref "U2") (pin "29_8") (pinfunction "GND_29_8") (pintype "power_in"))
      (node (ref "U2") (pin "29_9") (pinfunction "GND_29_9") (pintype "power_in"))
      (node (ref "U3") (pin "13") (pinfunction "GND_13") (pintype "power_in"))
      (node (ref "U4") (pin "1") (pinfunction "CTG_1") (pintype "power_in"))
      (node (ref "U4") (pin "4") (pinfunction "GND_4") (pintype "power_in"))
      (node (ref "U4") (pin "6") (pinfunction "QSTRT_6") (pintype "input"))
      (node (ref "U4") (pin "9") (pinfunction "EP_9") (pintype "power_in"))
    )
    (net (code "14") (name "GPIO8") (class "Default")
      (node (ref "R1") (pin "2") (pinfunction "2_2") (pintype "passive"))
      (node (ref "U2") (pin "10") (pinfunction "IO8_10") (pintype "bidirectional"))
    )
    (net (code "15") (name "I2C_PW") (class "Default")
      (node (ref "C1") (pin "1") (pinfunction "1_1") (pintype "passive"))
      (node (ref "C2") (pin "1") (pinfunction "1_1") (pintype "passive"))
      (node (ref "R1_PINH") (pin "2") (pinfunction "2_2") (pintype "passive"))
      (node (ref "R2-PINH") (pin "2") (pinfunction "2_2") (pintype "passive"))
      (node (ref "SENSOR2") (pin "2") (pinfunction "CSB_2") (pintype "input"))
      (node (ref "SENSOR2") (pin "6") (pinfunction "VDDIO_6") (pintype "power_in"))
      (node (ref "SENSOR2") (pin "8") (pinfunction "VDD_8") (pintype "power_in"))
      (node (ref "U2") (pin "17") (pinfunction "IO19_17") (pintype "bidirectional"))
    )
    (net (code "16") (name "INT_RTC") (class "Default")
      (node (ref "R1_PINH1") (pin "1") (pinfunction "1_1") (pintype "passive"))
      (node (ref "TP15") (pin "TP") (pinfunction "TP_TP") (pintype "input"))
      (node (ref "U2") (pin "8") (pinfunction "IO0_8") (pintype "bidirectional"))
      (node (ref "U3") (pin "3") (pinfunction "SQW/~{INT}_3") (pintype "output"))
    )
    (net (code "17") (name "IO{slash}BOOT") (class "Default")
      (node (ref "BOOT_BUTTON") (pin "3") (pinfunction "3_3") (pintype "passive"))
      (node (ref "BOOT_BUTTON") (pin "4") (pinfunction "4_4") (pintype "passive"))
      (node (ref "C6") (pin "1") (pinfunction "1_1") (pintype "passive"))
      (node (ref "R_BOOT") (pin "2") (pinfunction "2_2") (pintype "passive"))
      (node (ref "U2") (pin "15") (pinfunction "IO9_15") (pintype "bidirectional"))
    )
    (net (code "18") (name "IO{slash}CHANGE") (class "Default")
      (node (ref "C10") (pin "1") (pinfunction "1_1") (pintype "passive"))
      (node (ref "CHANGE_BUTTON") (pin "3") (pinfunction "3_3") (pintype "passive"))
      (node (ref "CHANGE_BUTTON") (pin "4") (pinfunction "4_4") (pintype "passive"))
      (node (ref "R_CHANGE") (pin "2") (pinfunction "2_2") (pintype "passive"))
      (node (ref "U2") (pin "23") (pinfunction "IO15_23") (pintype "bidirectional"))
    )
    (net (code "19") (name "MISO") (class "Default")
      (node (ref "D12") (pin "1") (pinfunction "1_1") (pintype "passive"))
      (node (ref "J4") (pin "P7") (pinfunction "DAT0_P7") (pintype "bidirectional"))
      (node (ref "R8") (pin "1") (pinfunction "1_1") (pintype "passive"))
      (node (ref "TP6") (pin "TP") (pinfunction "TP_TP") (pintype "input"))
      (node (ref "U1") (pin "2") (pinfunction "DO(IO1)_2") (pintype "bidirectional"))
      (node (ref "U2") (pin "27") (pinfunction "IO2_27") (pintype "bidirectional"))
    )
    (net (code "20") (name "MOSI") (class "Default")
      (node (ref "D11") (pin "1") (pinfunction "1_1") (pintype "passive"))
      (node (ref "J1") (pin "14") (pinfunction "14_14") (pintype "bidirectional"))
      (node (ref "J4") (pin "P3") (pinfunction "CMD_P3") (pintype "bidirectional"))
      (node (ref "R7") (pin "1") (pinfunction "1_1") (pintype "passive"))
      (node (ref "TP7") (pin "TP") (pinfunction "TP_TP") (pintype "input"))
      (node (ref "U1") (pin "5") (pinfunction "DI(IO0)_5") (pintype "bidirectional"))
      (node (ref "U2") (pin "7") (pinfunction "IO7_7") (pintype "bidirectional"))
    )
    (net (code "21") (name "Net-(CHG_LED-PadC)") (class "Default")
      (node (ref "CHG_LED") (pin "C") (pinfunction "C_C") (pintype "passive"))
      (node (ref "R1_BAT") (pin "2") (pinfunction "2_2") (pintype "passive"))
    )
    (net (code "22") (name "Net-(D2-CATHODE)") (class "Default")
      (node (ref "C1_BAT1") (pin "1") (pinfunction "1_1") (pintype "passive"))
      (node (ref "D2") (pin "1") (pinfunction "CATHODE_1") (pintype "bidirectional"))
      (node (ref "IC4") (pin "1") (pinfunction "VIN_1") (pintype "bidirectional"))
      (node (ref "IC4") (pin "3") (pinfunction "CE_3") (pintype "bidirectional"))
      (node (ref "Q1") (pin "2") (pinfunction "S_2") (pintype "bidirectional"))
    )
    (net (code "23") (name "Net-(D3-A)") (class "Default")
      (node (ref "C4") (pin "1") (pinfunction "1_1") (pintype "passive"))
      (node (ref "D3") (pin "2") (pinfunction "A_2") (pintype "bidirectional"))
      (node (ref "D4") (pin "1") (pinfunction "K_1") (pintype "bidirectional"))
    )
    (net (code "24") (name "Net-(D7-CATHODE)") (class "Default")
      (node (ref "D7") (pin "1") (pinfunction "CATHODE_1") (pintype "bidirectional"))
      (node (ref "R_CAPACITOR") (pin "1") (pinfunction "1_1") (pintype "passive"))
    )
    (net (code "25") (name "Net-(EPD_C1-Pad1)") (class "Default")
      (node (ref "EPD_C1") (pin "1") (pinfunction "1_1") (pintype "passive"))
      (node (ref "J1") (pin "4") (pinfunction "4_4") (pintype "bidirectional"))
    )
    (net (code "26") (name "Net-(EPD_C2-Pad1)") (class "Default")
      (node (ref "EPD_C2") (pin "1") (pinfunction "1_1") (pintype "passive"))
      (node (ref "J1") (pin "5") (pinfunction "5_5") (pintype "bidirectional"))
    )
    (net (code "27") (name "Net-(EPD_C6-Pad1)") (class "Default")
      (node (ref "EPD_C6") (pin "1") (pinfunction "1_1") (pintype "passive"))
      (node (ref "J1") (pin "18") (pinfunction "18_18") (pintype "bidirectional"))
    )
    (net (code "28") (name "Net-(EPD_C7-Pad1)") (class "Default")
      (node (ref "EPD_C7") (pin "1") (pinfunction "1_1") (pintype "passive"))
      (node (ref "J1") (pin "19") (pinfunction "19_19") (pintype "bidirectional"))
    )
    (net (code "29") (name "Net-(EPD_C8-Pad1)") (class "Default")
      (node (ref "EPD_C8") (pin "1") (pinfunction "1_1") (pintype "passive"))
      (node (ref "J1") (pin "20") (pinfunction "20_20") (pintype "bidirectional"))
    )
    (net (code "30") (name "Net-(EPD_C10-Pad1)") (class "Default")
      (node (ref "EPD_C10") (pin "1") (pinfunction "1_1") (pintype "passive"))
      (node (ref "J1") (pin "22") (pinfunction "22_22") (pintype "bidirectional"))
    )
    (net (code "31") (name "Net-(EPD_C12-Pad1)") (class "Default")
      (node (ref "EPD_C12") (pin "1") (pinfunction "1_1") (pintype "passive"))
      (node (ref "J1") (pin "24") (pinfunction "24_24") (pintype "bidirectional"))
    )
    (net (code "32") (name "Net-(IC1-CT)") (class "Default")
      (node (ref "C_DELAY") (pin "1") (pinfunction "1_1") (pintype "passive"))
      (node (ref "IC1") (pin "5") (pinfunction "CT_5") (pintype "bidirectional"))
    )
    (net (code "33") (name "Net-(J2-PadA5)") (class "Default")
      (node (ref "J2") (pin "A5") (pinfunction "A5_A5") (pintype "bidirectional"))
      (node (ref "R2-USB1") (pin "2") (pinfunction "2_2") (pintype "passive"))
    )
    (net (code "34") (name "Net-(J2-PadB5)") (class "Default")
      (node (ref "J2") (pin "B5") (pinfunction "B5_B5") (pintype "bidirectional"))
      (node (ref "R2-USB") (pin "1") (pinfunction "1_1") (pintype "passive"))
    )
    (net (code "35") (name "Net-(MCP73831-PROG)") (class "Default")
      (node (ref "MCP73831") (pin "5") (pinfunction "PROG_5") (pintype "input"))
      (node (ref "R2_BAT") (pin "2") (pinfunction "2_2") (pintype "passive"))
    )
    (net (code "36") (name "Net-(MCP73831-STAT)") (class "Default")
      (node (ref "MCP73831") (pin "1") (pinfunction "STAT_1") (pintype "output"))
      (node (ref "R1_BAT") (pin "1") (pinfunction "1_1") (pintype "passive"))
    )
    (net (code "37") (name "PREVGH") (class "Default")
      (node (ref "EPD_C9") (pin "1") (pinfunction "1_1") (pintype "passive"))
      (node (ref "J1") (pin "21") (pinfunction "21_21") (pintype "bidirectional"))
    )
    (net (code "38") (name "PREVGL") (class "Default")
      (node (ref "D4") (pin "2") (pinfunction "A_2") (pintype "bidirectional"))
      (node (ref "D5") (pin "1") (pinfunction "K_1") (pintype "bidirectional"))
      (node (ref "EPD_C11") (pin "1") (pinfunction "1_1") (pintype "passive"))
      (node (ref "J1") (pin "23") (pinfunction "23_23") (pintype "bidirectional"))
    )
    (net (code "39") (name "RESE") (class "Default")
      (node (ref "J1") (pin "3") (pinfunction "3_3") (pintype "bidirectional"))
      (node (ref "Q3") (pin "2") (pinfunction "S_2") (pintype "bidirectional"))
      (node (ref "R3") (pin "1") (pinfunction "1_1") (pintype "passive"))
    )
    (net (code "40") (name "RESE'") (class "Default")
      (node (ref "R2") (pin "2") (pinfunction "2_2") (pintype "passive"))
      (node (ref "R3") (pin "2") (pinfunction "2_2") (pintype "passive"))
      (node (ref "SJ1") (pin "2") (pinfunction "2_2") (pintype "passive"))
    )
    (net (code "41") (name "RESET") (class "Default")
      (node (ref "C5") (pin "1") (pinfunction "1_1") (pintype "passive"))
      (node (ref "IC1") (pin "1") (pinfunction "VOUT_1") (pintype "bidirectional"))
      (node (ref "RESET_BUTTON") (pin "3") (pinfunction "3_3") (pintype "passive"))
      (node (ref "RESET_BUTTON") (pin "4") (pinfunction "4_4") (pintype "passive"))
      (node (ref "R_RESET") (pin "2") (pinfunction "2_2") (pintype "passive"))
      (node (ref "U2") (pin "3") (pinfunction "EN_3") (pintype "input"))
    )
    (net (code "42") (name "RTC_RST") (class "Default")
      (node (ref "U2") (pin "16") (pinfunction "IO18_16") (pintype "bidirectional"))
      (node (ref "U3") (pin "4") (pinfunction "~{RST}_4") (pintype "input"))
    )
    (net (code "43") (name "RX") (class "Default")
      (node (ref "TP2") (pin "TP") (pinfunction "TP_TP") (pintype "input"))
      (node (ref "U2") (pin "24") (pinfunction "RXD0/GPIO17_24") (pintype "bidirectional"))
    )
    (net (code "44") (name "SCK") (class "Default")
      (node (ref "D10") (pin "1") (pinfunction "1_1") (pintype "passive"))
      (node (ref "J1") (pin "13") (pinfunction "13_13") (pintype "bidirectional"))
      (node (ref "J4") (pin "P5") (pinfunction "CLK_P5") (pintype "bidirectional"))
      (node (ref "R6") (pin "1") (pinfunction "1_1") (pintype "passive"))
      (node (ref "TP8") (pin "TP") (pinfunction "TP_TP") (pintype "input"))
      (node (ref "U1") (pin "6") (pinfunction "CLK_6") (pintype "input"))
      (node (ref "U2") (pin "6") (pinfunction "IO6_6") (pintype "bidirectional"))
    )
    (net (code "45") (name "SCL") (class "Default")
      (node (ref "J3") (pin "4") (pinfunction "4_4") (pintype "passive"))
      (node (ref "R2-PINH") (pin "1") (pinfunction "1_1") (pintype "passive"))
      (node (ref "SENSOR2") (pin "4") (pinfunction "SCK_4") (pintype "input"))
      (node (ref "U2") (pin "20") (pinfunction "IO22_20") (pintype "bidirectional"))
      (node (ref "U3") (pin "16") (pinfunction "SCL_16") (pintype "input"))
      (node (ref "U4") (pin "7") (pinfunction "SCL_7") (pintype "input"))
    )
    (net (code "46") (name "SDA") (class "Default")
      (node (ref "J3") (pin "3") (pinfunction "3_3") (pintype "passive"))
      (node (ref "R1_PINH") (pin "1") (pinfunction "1_1") (pintype "passive"))
      (node (ref "SENSOR2") (pin "3") (pinfunction "SDI_3") (pintype "bidirectional"))
      (node (ref "U2") (pin "19") (pinfunction "IO21_19") (pintype "bidirectional"))
      (node (ref "U3") (pin "15") (pinfunction "SDA_15") (pintype "bidirectional"))
      (node (ref "U4") (pin "8") (pinfunction "SDA_8") (pintype "bidirectional"))
    )
    (net (code "47") (name "SRC") (class "Default")
      (node (ref "C4") (pin "2") (pinfunction "2_2") (pintype "passive"))
      (node (ref "D5") (pin "2") (pinfunction "A_2") (pintype "bidirectional"))
      (node (ref "L1") (pin "1") (pinfunction "1_1") (pintype "passive"))
      (node (ref "Q3") (pin "3") (pinfunction "D_3") (pintype "bidirectional"))
    )
    (net (code "48") (name "SS_SD") (class "Default")
      (node (ref "D8") (pin "1") (pinfunction "1_1") (pintype "passive"))
      (node (ref "J4") (pin "P2") (pinfunction "CD/DAT3_P2") (pintype "bidirectional"))
      (node (ref "R10") (pin "1") (pinfunction "1_1") (pintype "passive"))
      (node (ref "U2") (pin "4") (pinfunction "IO4_4") (pintype "bidirectional"))
    )
    (net (code "49") (name "TX") (class "Default")
      (node (ref "TP1") (pin "TP") (pinfunction "TP_TP") (pintype "input"))
      (node (ref "U2") (pin "25") (pinfunction "TXD0/GPIO16_25") (pintype "bidirectional"))
    )
    (net (code "50") (name "USB_D+") (class "Default")
      (node (ref "D1") (pin "1") (pinfunction "I/O1_1_1") (pintype "bidirectional"))
      (node (ref "U2") (pin "14") (pinfunction "IO13_14") (pintype "bidirectional"))
    )
    (net (code "51") (name "USB_D-") (class "Default")
      (node (ref "D1") (pin "3") (pinfunction "I/O2_1_3") (pintype "bidirectional"))
      (node (ref "U2") (pin "13") (pinfunction "IO12_13") (pintype "bidirectional"))
    )
    (net (code "52") (name "VBAT") (class "Default")
      (node (ref "C2_BAT") (pin "1") (pinfunction "1_1") (pintype "passive"))
      (node (ref "MCP73831") (pin "3") (pinfunction "VBAT_3") (pintype "power_in"))
      (node (ref "Q1") (pin "3") (pinfunction "D_3") (pintype "bidirectional"))
      (node (ref "TP3") (pin "TP") (pinfunction "TP_TP") (pintype "input"))
      (node (ref "U4") (pin "2") (pinfunction "CELL_2") (pintype "power_in"))
      (node (ref "U4") (pin "3") (pinfunction "VDD_3") (pintype "power_in"))
    )
    (net (code "53") (name "VBUS") (class "Default")
      (node (ref "C1_BAT") (pin "1") (pinfunction "1_1") (pintype "passive"))
      (node (ref "C4_USB") (pin "1") (pinfunction "1_1") (pintype "passive"))
      (node (ref "C5_USB") (pin "1") (pinfunction "1_1") (pintype "passive"))
      (node (ref "CHG_LED") (pin "A") (pinfunction "A_A") (pintype "passive"))
      (node (ref "D1") (pin "5") (pinfunction "VBUS_5") (pintype "bidirectional"))
      (node (ref "D2") (pin "2") (pinfunction "ANODE_2") (pintype "bidirectional"))
      (node (ref "MCP73831") (pin "4") (pinfunction "VIN_4") (pintype "power_in"))
      (node (ref "PFMF.050.1") (pin "2") (pinfunction "2_2") (pintype "passive"))
      (node (ref "Q1") (pin "1") (pinfunction "G_1") (pintype "bidirectional"))
      (node (ref "R1_PWRUSB") (pin "2") (pinfunction "2_2") (pintype "passive"))
      (node (ref "TP14") (pin "TP") (pinfunction "TP_TP") (pintype "input"))
    )
    (net (code "54") (name "VRTC") (class "Default")
      (node (ref "C10_SUPERCAP") (pin "2") (pinfunction "2_2") (pintype "passive"))
      (node (ref "C8") (pin "1") (pinfunction "1_1") (pintype "passive"))
      (node (ref "R_CAPACITOR") (pin "2") (pinfunction "2_2") (pintype "passive"))
      (node (ref "U3") (pin "14") (pinfunction "VBAT_14") (pintype "power_in"))
    )
    (net (code "55") (name "VUSB") (class "Default")
      (node (ref "J2") (pin "A4") (pinfunction "A4_A4") (pintype "bidirectional"))
      (node (ref "J2") (pin "A9") (pinfunction "A9_A9") (pintype "bidirectional"))
      (node (ref "J2") (pin "B4") (pinfunction "B4_B4") (pintype "bidirectional"))
      (node (ref "J2") (pin "B9") (pinfunction "B9_B9") (pintype "bidirectional"))
      (node (ref "PFMF.050.1") (pin "1") (pinfunction "1_1") (pintype "passive"))
    )
    (net (code "56") (name "unconnected-(IC1-NC-Pad4)") (class "Default")
      (node (ref "IC1") (pin "4") (pinfunction "NC_4") (pintype "no_connect"))
    )
    (net (code "57") (name "unconnected-(IC4-NC-Pad4)") (class "Default")
      (node (ref "IC4") (pin "4") (pinfunction "NC_4") (pintype "no_connect"))
    )
    (net (code "58") (name "unconnected-(J1-Pad1)") (class "Default")
      (node (ref "J1") (pin "1") (pinfunction "1_1") (pintype "bidirectional"))
    )
    (net (code "59") (name "unconnected-(J1-Pad6)") (class "Default")
      (node (ref "J1") (pin "6") (pinfunction "6_6") (pintype "bidirectional"))
    )
    (net (code "60") (name "unconnected-(J1-Pad7)") (class "Default")
      (node (ref "J1") (pin "7") (pinfunction "7_7") (pintype "bidirectional"))
    )
    (net (code "61") (name "unconnected-(J2-PadA8)") (class "Default")
      (node (ref "J2") (pin "A8") (pinfunction "A8_A8") (pintype "bidirectional"))
    )
    (net (code "62") (name "unconnected-(J2-PadB8)") (class "Default")
      (node (ref "J2") (pin "B8") (pinfunction "B8_B8") (pintype "bidirectional"))
    )
    (net (code "63") (name "unconnected-(J4-DAT1-PadP8)") (class "Default")
      (node (ref "J4") (pin "P8") (pinfunction "DAT1_P8") (pintype "bidirectional"))
    )
    (net (code "64") (name "unconnected-(J4-DAT2-PadP1)") (class "Default")
      (node (ref "J4") (pin "P1") (pinfunction "DAT2_P1") (pintype "bidirectional"))
    )
    (net (code "65") (name "unconnected-(J4-DETECTION_1-PadS1)") (class "Default")
      (node (ref "J4") (pin "S1") (pinfunction "DETECTION_1_S1") (pintype "bidirectional"))
    )
    (net (code "66") (name "unconnected-(J4-DETECTION_2-PadS2)") (class "Default")
      (node (ref "J4") (pin "S2") (pinfunction "DETECTION_2_S2") (pintype "bidirectional"))
    )
    (net (code "67") (name "unconnected-(U2-NC-Pad22)") (class "Default")
      (node (ref "U2") (pin "22") (pinfunction "NC_22") (pintype "no_connect"))
    )
    (net (code "68") (name "unconnected-(U4-~{ALERT}-Pad5)") (class "Default")
      (node (ref "U4") (pin "5") (pinfunction "~{ALERT}_5") (pintype "output"))
    )
  )
)
